# host_1.net
KiCad netlist of a schematic drawn in EAGLE
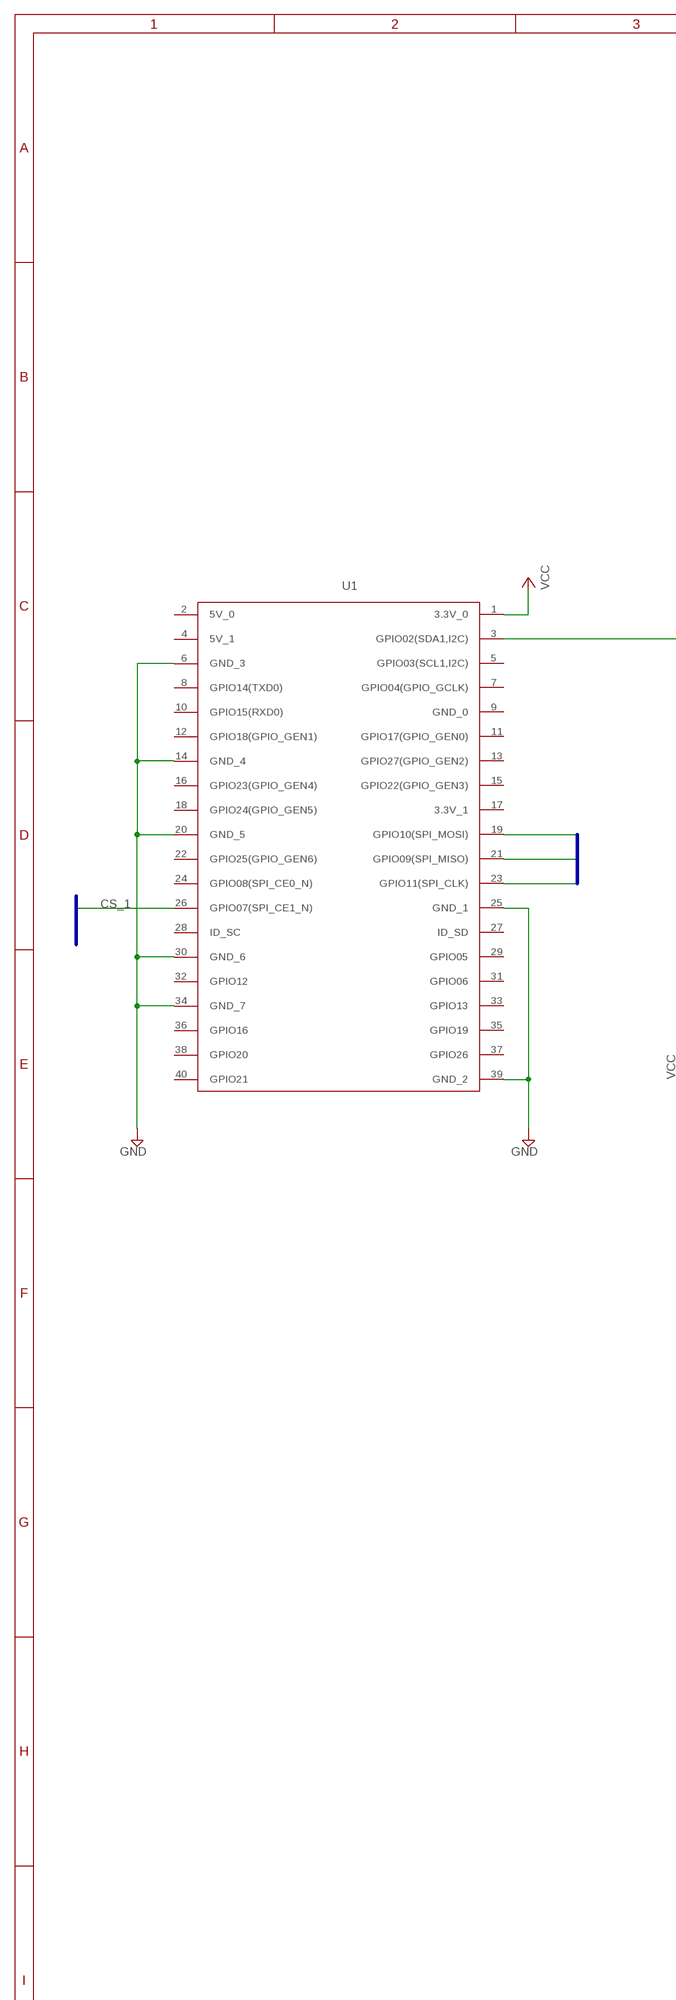
[diagram p0: schematic, sheet 1, part 1 of 2]
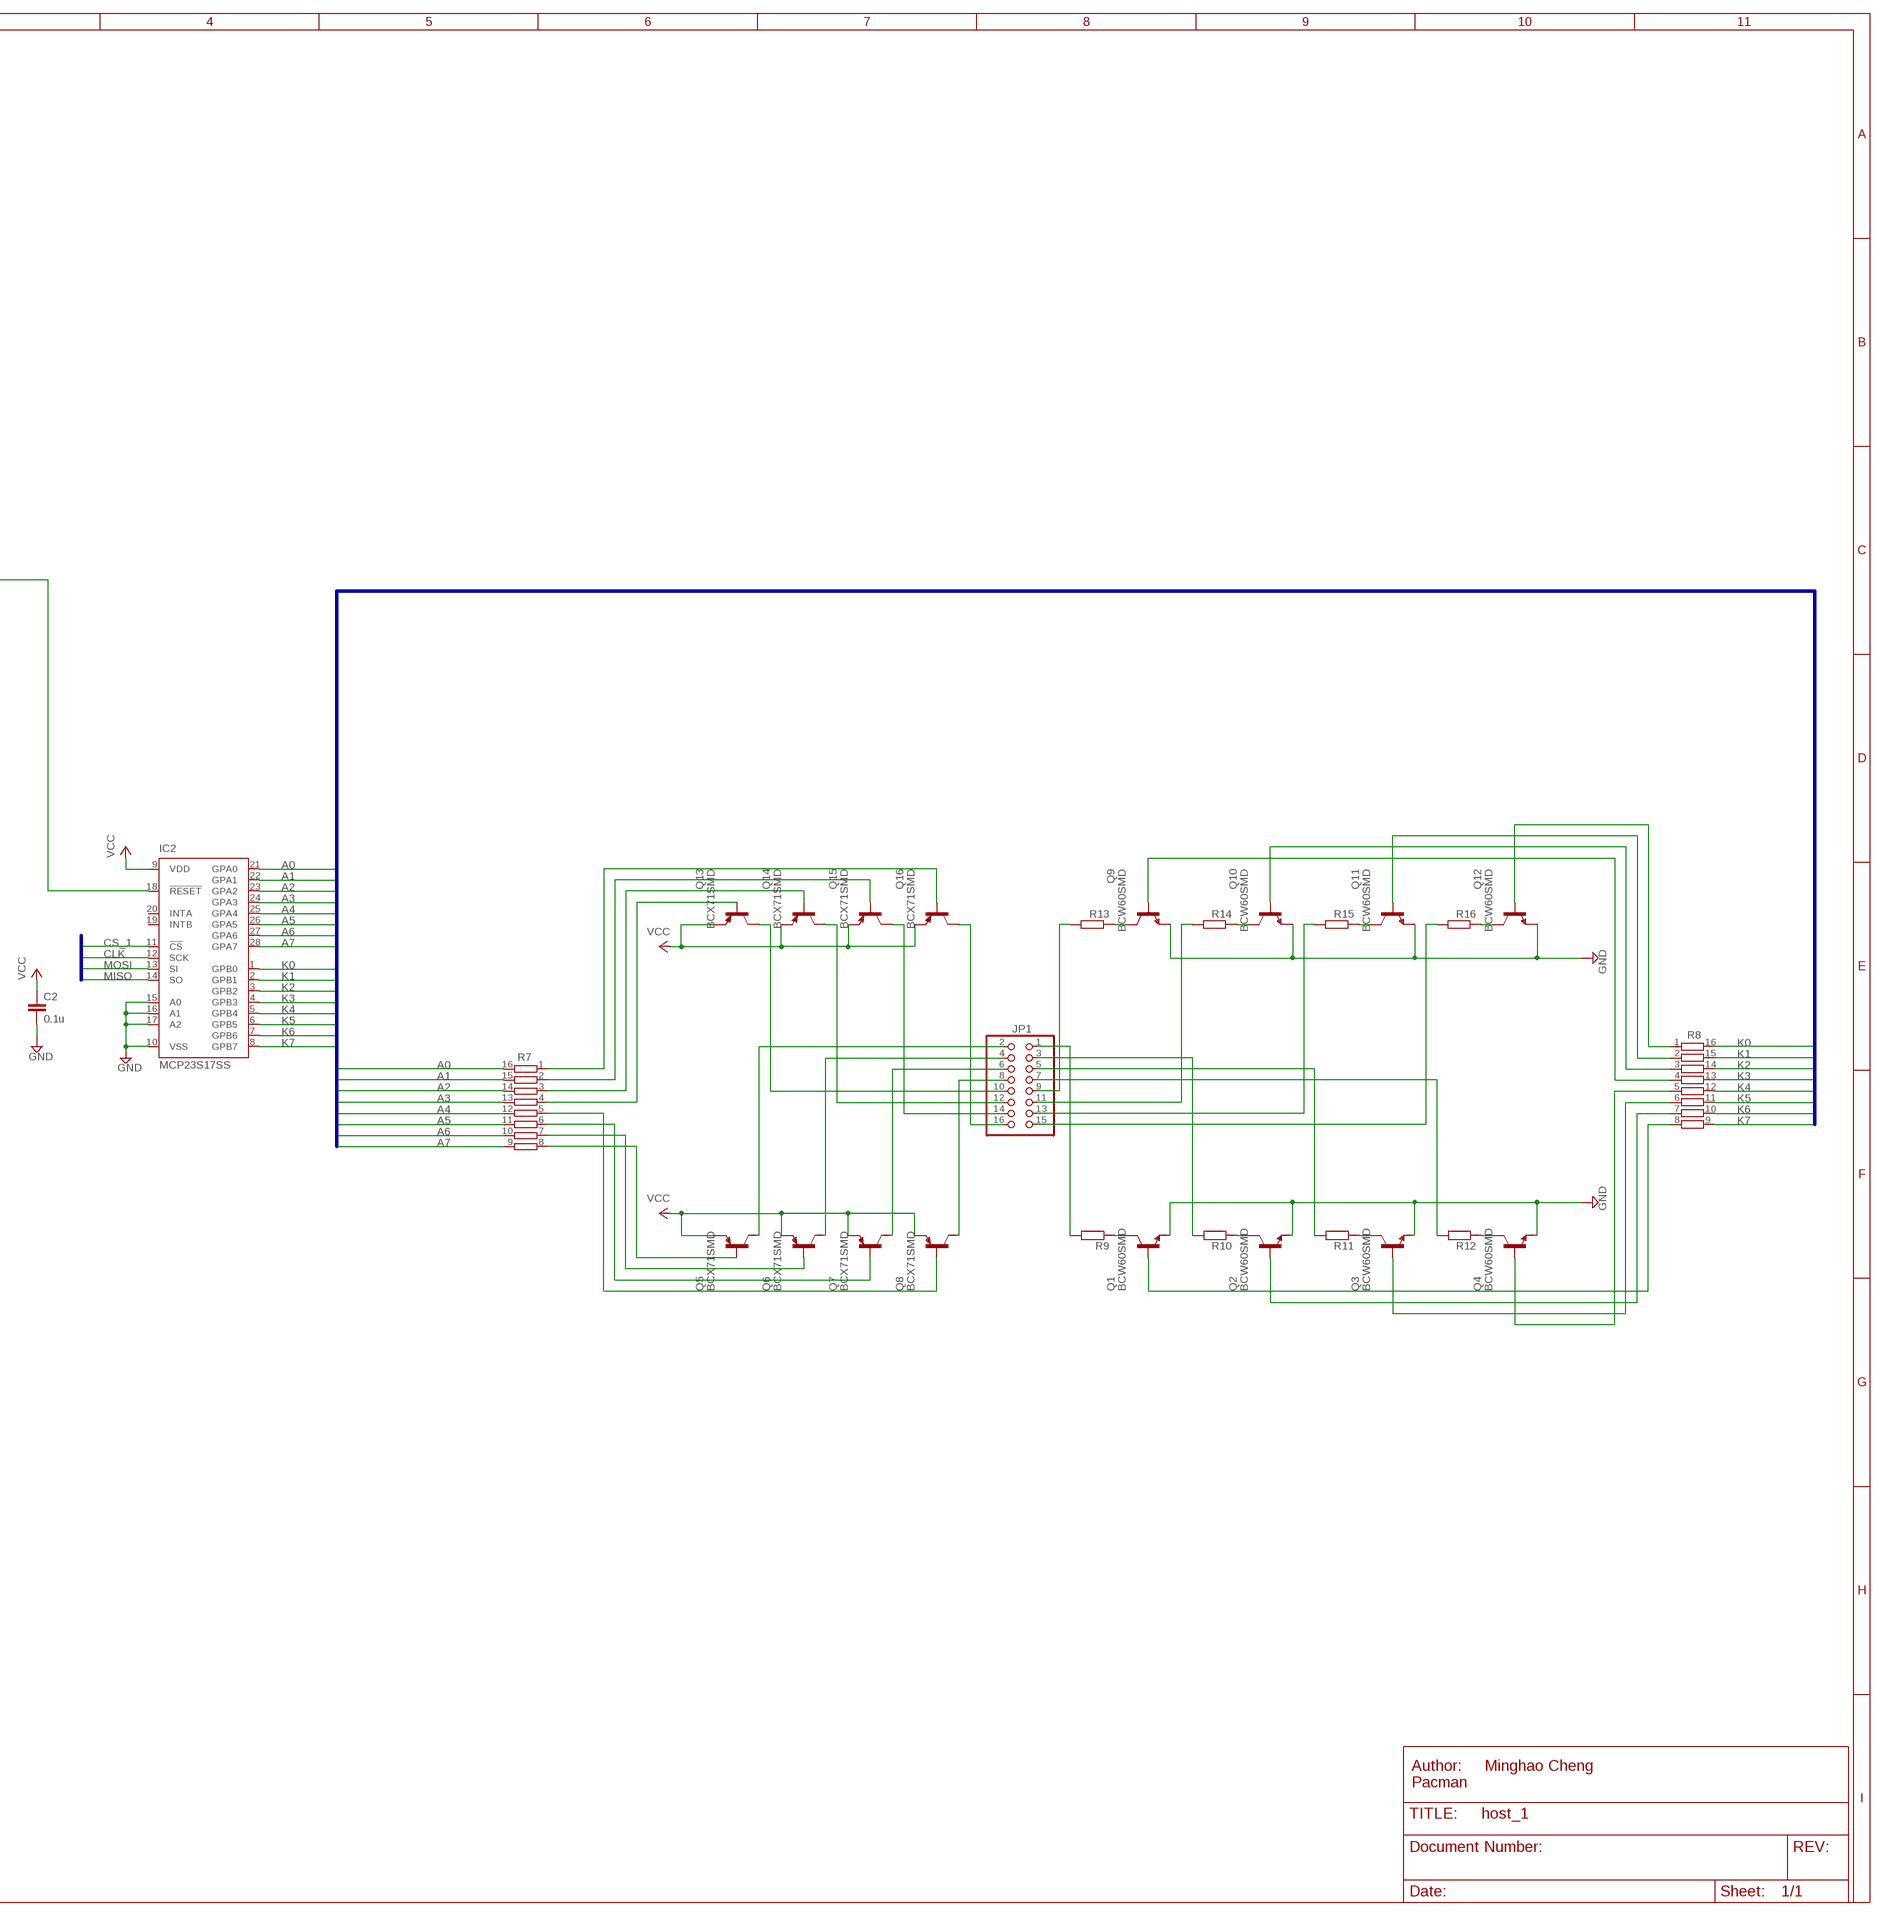
[diagram p1: schematic, sheet 1, part 2 of 2]

(export (version "E")
  (design (tool "Eeschema 10.0.6"))
  (components
    (comp (ref "C2")
      (value "0.1u")
      (footprint "eagle-import:C0805")
      (libsource (lib "eagle-import") (part "C-EUC0805"))
    )
    (comp (ref "IC2")
      (value "MCP23S17SS")
      (footprint "eagle-import:SSOP28")
      (fields (field (name "MF") "MICROCHIP") (field (name "MPN") "MCP23S17-E/SS"))
      (libsource (lib "eagle-import") (part "MCP23S17SS"))
    )
    (comp (ref "JP1")
      (value "PINHD-2X8")
      (footprint "eagle-import:2X08")
      (libsource (lib "eagle-import") (part "PINHD-2X8"))
    )
    (comp (ref "Q1")
      (value "BCW60SMD")
      (footprint "eagle-import:SOT23-BEC")
      (libsource (lib "eagle-import") (part "BCW60SMD"))
    )
    (comp (ref "Q2")
      (value "BCW60SMD")
      (footprint "eagle-import:SOT23-BEC")
      (libsource (lib "eagle-import") (part "BCW60SMD"))
    )
    (comp (ref "Q3")
      (value "BCW60SMD")
      (footprint "eagle-import:SOT23-BEC")
      (libsource (lib "eagle-import") (part "BCW60SMD"))
    )
    (comp (ref "Q4")
      (value "BCW60SMD")
      (footprint "eagle-import:SOT23-BEC")
      (libsource (lib "eagle-import") (part "BCW60SMD"))
    )
    (comp (ref "Q5")
      (value "BCX71SMD")
      (footprint "eagle-import:SOT23")
      (libsource (lib "eagle-import") (part "BCX71SMD"))
    )
    (comp (ref "Q6")
      (value "BCX71SMD")
      (footprint "eagle-import:SOT23")
      (libsource (lib "eagle-import") (part "BCX71SMD"))
    )
    (comp (ref "Q7")
      (value "BCX71SMD")
      (footprint "eagle-import:SOT23")
      (libsource (lib "eagle-import") (part "BCX71SMD"))
    )
    (comp (ref "Q8")
      (value "BCX71SMD")
      (footprint "eagle-import:SOT23")
      (libsource (lib "eagle-import") (part "BCX71SMD"))
    )
    (comp (ref "Q9")
      (value "BCW60SMD")
      (footprint "eagle-import:SOT23-BEC")
      (libsource (lib "eagle-import") (part "BCW60SMD"))
    )
    (comp (ref "Q10")
      (value "BCW60SMD")
      (footprint "eagle-import:SOT23-BEC")
      (libsource (lib "eagle-import") (part "BCW60SMD"))
    )
    (comp (ref "Q11")
      (value "BCW60SMD")
      (footprint "eagle-import:SOT23-BEC")
      (libsource (lib "eagle-import") (part "BCW60SMD"))
    )
    (comp (ref "Q12")
      (value "BCW60SMD")
      (footprint "eagle-import:SOT23-BEC")
      (libsource (lib "eagle-import") (part "BCW60SMD"))
    )
    (comp (ref "Q13")
      (value "BCX71SMD")
      (footprint "eagle-import:SOT23")
      (libsource (lib "eagle-import") (part "BCX71SMD"))
    )
    (comp (ref "Q14")
      (value "BCX71SMD")
      (footprint "eagle-import:SOT23")
      (libsource (lib "eagle-import") (part "BCX71SMD"))
    )
    (comp (ref "Q15")
      (value "BCX71SMD")
      (footprint "eagle-import:SOT23")
      (libsource (lib "eagle-import") (part "BCX71SMD"))
    )
    (comp (ref "Q16")
      (value "BCX71SMD")
      (footprint "eagle-import:SOT23")
      (libsource (lib "eagle-import") (part "BCX71SMD"))
    )
    (comp (ref "R7")
      (value "4816P-T01")
      (footprint "eagle-import:4816P")
      (fields (field (name "MF") "BOURNS, INC.") (field (name "MPN") "4816P-T01-684LF"))
      (libsource (lib "eagle-import") (part "4816P-T01"))
    )
    (comp (ref "R8")
      (value "4816P-T01")
      (footprint "eagle-import:4816P")
      (fields (field (name "MF") "BOURNS, INC.") (field (name "MPN") "4816P-T01-684LF"))
      (libsource (lib "eagle-import") (part "4816P-T01"))
    )
    (comp (ref "R9")
      (value "4.7K")
      (footprint "eagle-import:R0805")
      (libsource (lib "eagle-import") (part "R-EU_R0805"))
    )
    (comp (ref "R10")
      (value "4.7K")
      (footprint "eagle-import:R0805")
      (libsource (lib "eagle-import") (part "R-EU_R0805"))
    )
    (comp (ref "R11")
      (value "4.7K")
      (footprint "eagle-import:R0805")
      (libsource (lib "eagle-import") (part "R-EU_R0805"))
    )
    (comp (ref "R12")
      (value "4.7K")
      (footprint "eagle-import:R0805")
      (libsource (lib "eagle-import") (part "R-EU_R0805"))
    )
    (comp (ref "R13")
      (value "4.7K")
      (footprint "eagle-import:R0805")
      (libsource (lib "eagle-import") (part "R-EU_R0805"))
    )
    (comp (ref "R14")
      (value "4.7K")
      (footprint "eagle-import:R0805")
      (libsource (lib "eagle-import") (part "R-EU_R0805"))
    )
    (comp (ref "R15")
      (value "4.7K")
      (footprint "eagle-import:R0805")
      (libsource (lib "eagle-import") (part "R-EU_R0805"))
    )
    (comp (ref "R16")
      (value "4.7K")
      (footprint "eagle-import:R0805")
      (libsource (lib "eagle-import") (part "R-EU_R0805"))
    )
    (comp (ref "U1")
      (value "RASPI3_GPIO")
      (footprint "eagle-import:FE20-2")
      (libsource (lib "eagle-import") (part "RASPI3_GPIO"))
    )
  )
  (nets
    (net (code "3") (name "/A0") (class "Default")
      (node (ref "IC2") (pin "21") (pinfunction "GPA0_21") (pintype "bidirectional"))
      (node (ref "R7") (pin "16") (pinfunction "16_16") (pintype "passive"))
    )
    (net (code "4") (name "/A1") (class "Default")
      (node (ref "IC2") (pin "22") (pinfunction "GPA1_22") (pintype "bidirectional"))
      (node (ref "R7") (pin "15") (pinfunction "15_15") (pintype "passive"))
    )
    (net (code "5") (name "/A2") (class "Default")
      (node (ref "IC2") (pin "23") (pinfunction "GPA2_23") (pintype "bidirectional"))
      (node (ref "R7") (pin "14") (pinfunction "14_14") (pintype "passive"))
    )
    (net (code "6") (name "/A3") (class "Default")
      (node (ref "IC2") (pin "24") (pinfunction "GPA3_24") (pintype "bidirectional"))
      (node (ref "R7") (pin "13") (pinfunction "13_13") (pintype "passive"))
    )
    (net (code "7") (name "/A4") (class "Default")
      (node (ref "IC2") (pin "25") (pinfunction "GPA4_25") (pintype "bidirectional"))
      (node (ref "R7") (pin "12") (pinfunction "12_12") (pintype "passive"))
    )
    (net (code "8") (name "/A5") (class "Default")
      (node (ref "IC2") (pin "26") (pinfunction "GPA5_26") (pintype "bidirectional"))
      (node (ref "R7") (pin "11") (pinfunction "11_11") (pintype "passive"))
    )
    (net (code "9") (name "/A6") (class "Default")
      (node (ref "IC2") (pin "27") (pinfunction "GPA6_27") (pintype "bidirectional"))
      (node (ref "R7") (pin "10") (pinfunction "10_10") (pintype "passive"))
    )
    (net (code "10") (name "/A7") (class "Default")
      (node (ref "IC2") (pin "28") (pinfunction "GPA7_28") (pintype "bidirectional"))
      (node (ref "R7") (pin "9") (pinfunction "9_9") (pintype "passive"))
    )
    (net (code "11") (name "/CLK") (class "Default")
      (node (ref "IC2") (pin "12") (pinfunction "SCK_12") (pintype "input"))
      (node (ref "U1") (pin "23") (pinfunction "GPIO11(SPI_CLK)_23") (pintype "bidirectional"))
    )
    (net (code "12") (name "/CS_1") (class "Default")
      (node (ref "IC2") (pin "11") (pinfunction "~{CS}_11") (pintype "input"))
      (node (ref "U1") (pin "26") (pinfunction "GPIO07(SPI_CE1_N)_26") (pintype "bidirectional"))
    )
    (net (code "13") (name "/K0") (class "Default")
      (node (ref "IC2") (pin "1") (pinfunction "GPB0_1") (pintype "bidirectional"))
      (node (ref "R8") (pin "16") (pinfunction "16_16") (pintype "passive"))
    )
    (net (code "14") (name "/K1") (class "Default")
      (node (ref "IC2") (pin "2") (pinfunction "GPB1_2") (pintype "bidirectional"))
      (node (ref "R8") (pin "15") (pinfunction "15_15") (pintype "passive"))
    )
    (net (code "15") (name "/K2") (class "Default")
      (node (ref "IC2") (pin "3") (pinfunction "GPB2_3") (pintype "bidirectional"))
      (node (ref "R8") (pin "14") (pinfunction "14_14") (pintype "passive"))
    )
    (net (code "16") (name "/K3") (class "Default")
      (node (ref "IC2") (pin "4") (pinfunction "GPB3_4") (pintype "bidirectional"))
      (node (ref "R8") (pin "13") (pinfunction "13_13") (pintype "passive"))
    )
    (net (code "17") (name "/K4") (class "Default")
      (node (ref "IC2") (pin "5") (pinfunction "GPB4_5") (pintype "bidirectional"))
      (node (ref "R8") (pin "12") (pinfunction "12_12") (pintype "passive"))
    )
    (net (code "18") (name "/K5") (class "Default")
      (node (ref "IC2") (pin "6") (pinfunction "GPB5_6") (pintype "bidirectional"))
      (node (ref "R8") (pin "11") (pinfunction "11_11") (pintype "passive"))
    )
    (net (code "19") (name "/K6") (class "Default")
      (node (ref "IC2") (pin "7") (pinfunction "GPB6_7") (pintype "bidirectional"))
      (node (ref "R8") (pin "10") (pinfunction "10_10") (pintype "passive"))
    )
    (net (code "20") (name "/K7") (class "Default")
      (node (ref "IC2") (pin "8") (pinfunction "GPB7_8") (pintype "bidirectional"))
      (node (ref "R8") (pin "9") (pinfunction "9_9") (pintype "passive"))
    )
    (net (code "21") (name "/MISO") (class "Default")
      (node (ref "IC2") (pin "14") (pinfunction "SO_14") (pintype "output"))
      (node (ref "U1") (pin "21") (pinfunction "GPIO09(SPI_MISO)_21") (pintype "bidirectional"))
    )
    (net (code "22") (name "/SPI_PI:CLK") (class "Default")
      (node (ref "IC2") (pin "13") (pinfunction "SI_13") (pintype "input"))
      (node (ref "U1") (pin "19") (pinfunction "GPIO10(SPI_MOSI)_19") (pintype "bidirectional"))
    )
    (net (code "24") (name "GND") (class "Default")
      (node (ref "C2") (pin "2") (pinfunction "2_2") (pintype "passive"))
      (node (ref "IC2") (pin "10") (pinfunction "VSS_10") (pintype "power_in"))
      (node (ref "IC2") (pin "15") (pinfunction "A0_15") (pintype "input"))
      (node (ref "IC2") (pin "16") (pinfunction "A1_16") (pintype "input"))
      (node (ref "IC2") (pin "17") (pinfunction "A2_17") (pintype "input"))
      (node (ref "Q1") (pin "E") (pinfunction "E_E") (pintype "passive"))
      (node (ref "Q10") (pin "E") (pinfunction "E_E") (pintype "passive"))
      (node (ref "Q11") (pin "E") (pinfunction "E_E") (pintype "passive"))
      (node (ref "Q12") (pin "E") (pinfunction "E_E") (pintype "passive"))
      (node (ref "Q2") (pin "E") (pinfunction "E_E") (pintype "passive"))
      (node (ref "Q3") (pin "E") (pinfunction "E_E") (pintype "passive"))
      (node (ref "Q4") (pin "E") (pinfunction "E_E") (pintype "passive"))
      (node (ref "Q9") (pin "E") (pinfunction "E_E") (pintype "passive"))
      (node (ref "U1") (pin "14") (pinfunction "GND_4_14") (pintype "bidirectional"))
      (node (ref "U1") (pin "20") (pinfunction "GND_5_20") (pintype "bidirectional"))
      (node (ref "U1") (pin "25") (pinfunction "GND_1_25") (pintype "bidirectional"))
      (node (ref "U1") (pin "30") (pinfunction "GND_6_30") (pintype "bidirectional"))
      (node (ref "U1") (pin "34") (pinfunction "GND_7_34") (pintype "bidirectional"))
      (node (ref "U1") (pin "39") (pinfunction "GND_2_39") (pintype "bidirectional"))
      (node (ref "U1") (pin "6") (pinfunction "GND_3_6") (pintype "bidirectional"))
    )
    (net (code "25") (name "Net-(IC2-~{RESET})") (class "Default")
      (node (ref "IC2") (pin "18") (pinfunction "~{RESET}_18") (pintype "input"))
      (node (ref "U1") (pin "3") (pinfunction "GPIO02(SDA1,I2C)_3") (pintype "bidirectional"))
    )
    (net (code "26") (name "Net-(JP1-Pad1)") (class "Default")
      (node (ref "JP1") (pin "1") (pinfunction "1_1") (pintype "passive"))
      (node (ref "R9") (pin "2") (pinfunction "2_2") (pintype "passive"))
    )
    (net (code "27") (name "Net-(JP1-Pad3)") (class "Default")
      (node (ref "JP1") (pin "3") (pinfunction "3_3") (pintype "passive"))
      (node (ref "R10") (pin "2") (pinfunction "2_2") (pintype "passive"))
    )
    (net (code "28") (name "Net-(JP1-Pad5)") (class "Default")
      (node (ref "JP1") (pin "5") (pinfunction "5_5") (pintype "passive"))
      (node (ref "R11") (pin "2") (pinfunction "2_2") (pintype "passive"))
    )
    (net (code "29") (name "Net-(JP1-Pad7)") (class "Default")
      (node (ref "JP1") (pin "7") (pinfunction "7_7") (pintype "passive"))
      (node (ref "R12") (pin "2") (pinfunction "2_2") (pintype "passive"))
    )
    (net (code "30") (name "Net-(JP1-Pad9)") (class "Default")
      (node (ref "JP1") (pin "9") (pinfunction "9_9") (pintype "passive"))
      (node (ref "R13") (pin "2") (pinfunction "2_2") (pintype "passive"))
    )
    (net (code "31") (name "Net-(JP1-Pad11)") (class "Default")
      (node (ref "JP1") (pin "11") (pinfunction "11_11") (pintype "passive"))
      (node (ref "R14") (pin "2") (pinfunction "2_2") (pintype "passive"))
    )
    (net (code "32") (name "Net-(JP1-Pad13)") (class "Default")
      (node (ref "JP1") (pin "13") (pinfunction "13_13") (pintype "passive"))
      (node (ref "R15") (pin "2") (pinfunction "2_2") (pintype "passive"))
    )
    (net (code "33") (name "Net-(JP1-Pad15)") (class "Default")
      (node (ref "JP1") (pin "15") (pinfunction "15_15") (pintype "passive"))
      (node (ref "R16") (pin "2") (pinfunction "2_2") (pintype "passive"))
    )
    (net (code "34") (name "Net-(Q1-PadB)") (class "Default")
      (node (ref "Q1") (pin "B") (pinfunction "B_B") (pintype "passive"))
      (node (ref "R8") (pin "8") (pinfunction "8_8") (pintype "passive"))
    )
    (net (code "35") (name "Net-(Q1-PadC)") (class "Default")
      (node (ref "Q1") (pin "C") (pinfunction "C_C") (pintype "passive"))
      (node (ref "R9") (pin "1") (pinfunction "1_1") (pintype "passive"))
    )
    (net (code "36") (name "Net-(Q2-PadB)") (class "Default")
      (node (ref "Q2") (pin "B") (pinfunction "B_B") (pintype "passive"))
      (node (ref "R8") (pin "7") (pinfunction "7_7") (pintype "passive"))
    )
    (net (code "37") (name "Net-(Q2-PadC)") (class "Default")
      (node (ref "Q2") (pin "C") (pinfunction "C_C") (pintype "passive"))
      (node (ref "R10") (pin "1") (pinfunction "1_1") (pintype "passive"))
    )
    (net (code "38") (name "Net-(Q3-PadB)") (class "Default")
      (node (ref "Q3") (pin "B") (pinfunction "B_B") (pintype "passive"))
      (node (ref "R8") (pin "6") (pinfunction "6_6") (pintype "passive"))
    )
    (net (code "39") (name "Net-(Q3-PadC)") (class "Default")
      (node (ref "Q3") (pin "C") (pinfunction "C_C") (pintype "passive"))
      (node (ref "R11") (pin "1") (pinfunction "1_1") (pintype "passive"))
    )
    (net (code "40") (name "Net-(Q4-PadB)") (class "Default")
      (node (ref "Q4") (pin "B") (pinfunction "B_B") (pintype "passive"))
      (node (ref "R8") (pin "5") (pinfunction "5_5") (pintype "passive"))
    )
    (net (code "41") (name "Net-(Q4-PadC)") (class "Default")
      (node (ref "Q4") (pin "C") (pinfunction "C_C") (pintype "passive"))
      (node (ref "R12") (pin "1") (pinfunction "1_1") (pintype "passive"))
    )
    (net (code "42") (name "Net-(Q5-B)") (class "Default")
      (node (ref "Q5") (pin "1") (pinfunction "B_1") (pintype "passive"))
      (node (ref "R7") (pin "8") (pinfunction "8_8") (pintype "passive"))
    )
    (net (code "43") (name "Net-(Q5-C)") (class "Default")
      (node (ref "JP1") (pin "2") (pinfunction "2_2") (pintype "passive"))
      (node (ref "Q5") (pin "3") (pinfunction "C_3") (pintype "passive"))
    )
    (net (code "44") (name "Net-(Q6-B)") (class "Default")
      (node (ref "Q6") (pin "1") (pinfunction "B_1") (pintype "passive"))
      (node (ref "R7") (pin "7") (pinfunction "7_7") (pintype "passive"))
    )
    (net (code "45") (name "Net-(Q6-C)") (class "Default")
      (node (ref "JP1") (pin "4") (pinfunction "4_4") (pintype "passive"))
      (node (ref "Q6") (pin "3") (pinfunction "C_3") (pintype "passive"))
    )
    (net (code "46") (name "Net-(Q7-B)") (class "Default")
      (node (ref "Q7") (pin "1") (pinfunction "B_1") (pintype "passive"))
      (node (ref "R7") (pin "6") (pinfunction "6_6") (pintype "passive"))
    )
    (net (code "47") (name "Net-(Q7-C)") (class "Default")
      (node (ref "JP1") (pin "6") (pinfunction "6_6") (pintype "passive"))
      (node (ref "Q7") (pin "3") (pinfunction "C_3") (pintype "passive"))
    )
    (net (code "48") (name "Net-(Q8-B)") (class "Default")
      (node (ref "Q8") (pin "1") (pinfunction "B_1") (pintype "passive"))
      (node (ref "R7") (pin "5") (pinfunction "5_5") (pintype "passive"))
    )
    (net (code "49") (name "Net-(Q8-C)") (class "Default")
      (node (ref "JP1") (pin "8") (pinfunction "8_8") (pintype "passive"))
      (node (ref "Q8") (pin "3") (pinfunction "C_3") (pintype "passive"))
    )
    (net (code "50") (name "Net-(Q9-PadB)") (class "Default")
      (node (ref "Q9") (pin "B") (pinfunction "B_B") (pintype "passive"))
      (node (ref "R8") (pin "4") (pinfunction "4_4") (pintype "passive"))
    )
    (net (code "51") (name "Net-(Q9-PadC)") (class "Default")
      (node (ref "Q9") (pin "C") (pinfunction "C_C") (pintype "passive"))
      (node (ref "R13") (pin "1") (pinfunction "1_1") (pintype "passive"))
    )
    (net (code "52") (name "Net-(Q10-PadB)") (class "Default")
      (node (ref "Q10") (pin "B") (pinfunction "B_B") (pintype "passive"))
      (node (ref "R8") (pin "3") (pinfunction "3_3") (pintype "passive"))
    )
    (net (code "53") (name "Net-(Q10-PadC)") (class "Default")
      (node (ref "Q10") (pin "C") (pinfunction "C_C") (pintype "passive"))
      (node (ref "R14") (pin "1") (pinfunction "1_1") (pintype "passive"))
    )
    (net (code "54") (name "Net-(Q11-PadB)") (class "Default")
      (node (ref "Q11") (pin "B") (pinfunction "B_B") (pintype "passive"))
      (node (ref "R8") (pin "2") (pinfunction "2_2") (pintype "passive"))
    )
    (net (code "55") (name "Net-(Q11-PadC)") (class "Default")
      (node (ref "Q11") (pin "C") (pinfunction "C_C") (pintype "passive"))
      (node (ref "R15") (pin "1") (pinfunction "1_1") (pintype "passive"))
    )
    (net (code "56") (name "Net-(Q12-PadB)") (class "Default")
      (node (ref "Q12") (pin "B") (pinfunction "B_B") (pintype "passive"))
      (node (ref "R8") (pin "1") (pinfunction "1_1") (pintype "passive"))
    )
    (net (code "57") (name "Net-(Q12-PadC)") (class "Default")
      (node (ref "Q12") (pin "C") (pinfunction "C_C") (pintype "passive"))
      (node (ref "R16") (pin "1") (pinfunction "1_1") (pintype "passive"))
    )
    (net (code "58") (name "Net-(Q13-B)") (class "Default")
      (node (ref "Q13") (pin "1") (pinfunction "B_1") (pintype "passive"))
      (node (ref "R7") (pin "4") (pinfunction "4_4") (pintype "passive"))
    )
    (net (code "59") (name "Net-(Q13-C)") (class "Default")
      (node (ref "JP1") (pin "10") (pinfunction "10_10") (pintype "passive"))
      (node (ref "Q13") (pin "3") (pinfunction "C_3") (pintype "passive"))
    )
    (net (code "60") (name "Net-(Q14-B)") (class "Default")
      (node (ref "Q14") (pin "1") (pinfunction "B_1") (pintype "passive"))
      (node (ref "R7") (pin "3") (pinfunction "3_3") (pintype "passive"))
    )
    (net (code "61") (name "Net-(Q14-C)") (class "Default")
      (node (ref "JP1") (pin "12") (pinfunction "12_12") (pintype "passive"))
      (node (ref "Q14") (pin "3") (pinfunction "C_3") (pintype "passive"))
    )
    (net (code "62") (name "Net-(Q15-B)") (class "Default")
      (node (ref "Q15") (pin "1") (pinfunction "B_1") (pintype "passive"))
      (node (ref "R7") (pin "2") (pinfunction "2_2") (pintype "passive"))
    )
    (net (code "63") (name "Net-(Q15-C)") (class "Default")
      (node (ref "JP1") (pin "14") (pinfunction "14_14") (pintype "passive"))
      (node (ref "Q15") (pin "3") (pinfunction "C_3") (pintype "passive"))
    )
    (net (code "64") (name "Net-(Q16-B)") (class "Default")
      (node (ref "Q16") (pin "1") (pinfunction "B_1") (pintype "passive"))
      (node (ref "R7") (pin "1") (pinfunction "1_1") (pintype "passive"))
    )
    (net (code "65") (name "Net-(Q16-C)") (class "Default")
      (node (ref "JP1") (pin "16") (pinfunction "16_16") (pintype "passive"))
      (node (ref "Q16") (pin "3") (pinfunction "C_3") (pintype "passive"))
    )
    (net (code "66") (name "VCC") (class "Default")
      (node (ref "C2") (pin "1") (pinfunction "1_1") (pintype "passive"))
      (node (ref "IC2") (pin "9") (pinfunction "VDD_9") (pintype "power_in"))
      (node (ref "Q13") (pin "2") (pinfunction "E_2") (pintype "passive"))
      (node (ref "Q14") (pin "2") (pinfunction "E_2") (pintype "passive"))
      (node (ref "Q15") (pin "2") (pinfunction "E_2") (pintype "passive"))
      (node (ref "Q16") (pin "2") (pinfunction "E_2") (pintype "passive"))
      (node (ref "Q5") (pin "2") (pinfunction "E_2") (pintype "passive"))
      (node (ref "Q6") (pin "2") (pinfunction "E_2") (pintype "passive"))
      (node (ref "Q7") (pin "2") (pinfunction "E_2") (pintype "passive"))
      (node (ref "Q8") (pin "2") (pinfunction "E_2") (pintype "passive"))
      (node (ref "U1") (pin "1") (pinfunction "3.3V_0_1") (pintype "bidirectional"))
    )
    (net (code "67") (name "unconnected-(IC2-INTA-Pad20)") (class "Default")
      (node (ref "IC2") (pin "20") (pinfunction "INTA_20") (pintype "output"))
    )
    (net (code "68") (name "unconnected-(IC2-INTB-Pad19)") (class "Default")
      (node (ref "IC2") (pin "19") (pinfunction "INTB_19") (pintype "output"))
    )
    (net (code "69") (name "unconnected-(U1-3.3V_1-Pad17)") (class "Default")
      (node (ref "U1") (pin "17") (pinfunction "3.3V_1_17") (pintype "bidirectional"))
    )
    (net (code "70") (name "unconnected-(U1-5V_0-Pad2)") (class "Default")
      (node (ref "U1") (pin "2") (pinfunction "5V_0_2") (pintype "bidirectional"))
    )
    (net (code "71") (name "unconnected-(U1-5V_1-Pad4)") (class "Default")
      (node (ref "U1") (pin "4") (pinfunction "5V_1_4") (pintype "bidirectional"))
    )
    (net (code "72") (name "unconnected-(U1-GND_0-Pad9)") (class "Default")
      (node (ref "U1") (pin "9") (pinfunction "GND_0_9") (pintype "bidirectional"))
    )
    (net (code "73") (name "unconnected-(U1-GPIO03(SCL1,I2C)-Pad5)") (class "Default")
      (node (ref "U1") (pin "5") (pinfunction "GPIO03(SCL1,I2C)_5") (pintype "bidirectional"))
    )
    (net (code "74") (name "unconnected-(U1-GPIO04(GPIO_GCLK)-Pad7)") (class "Default")
      (node (ref "U1") (pin "7") (pinfunction "GPIO04(GPIO_GCLK)_7") (pintype "bidirectional"))
    )
    (net (code "75") (name "unconnected-(U1-GPIO05-Pad29)") (class "Default")
      (node (ref "U1") (pin "29") (pinfunction "GPIO05_29") (pintype "bidirectional"))
    )
    (net (code "76") (name "unconnected-(U1-GPIO06-Pad31)") (class "Default")
      (node (ref "U1") (pin "31") (pinfunction "GPIO06_31") (pintype "bidirectional"))
    )
    (net (code "77") (name "unconnected-(U1-GPIO08(SPI_CE0_N)-Pad24)") (class "Default")
      (node (ref "U1") (pin "24") (pinfunction "GPIO08(SPI_CE0_N)_24") (pintype "bidirectional"))
    )
    (net (code "78") (name "unconnected-(U1-GPIO12-Pad32)") (class "Default")
      (node (ref "U1") (pin "32") (pinfunction "GPIO12_32") (pintype "bidirectional"))
    )
    (net (code "79") (name "unconnected-(U1-GPIO13-Pad33)") (class "Default")
      (node (ref "U1") (pin "33") (pinfunction "GPIO13_33") (pintype "bidirectional"))
    )
    (net (code "80") (name "unconnected-(U1-GPIO14(TXD0)-Pad8)") (class "Default")
      (node (ref "U1") (pin "8") (pinfunction "GPIO14(TXD0)_8") (pintype "bidirectional"))
    )
    (net (code "81") (name "unconnected-(U1-GPIO15(RXD0)-Pad10)") (class "Default")
      (node (ref "U1") (pin "10") (pinfunction "GPIO15(RXD0)_10") (pintype "bidirectional"))
    )
    (net (code "82") (name "unconnected-(U1-GPIO16-Pad36)") (class "Default")
      (node (ref "U1") (pin "36") (pinfunction "GPIO16_36") (pintype "bidirectional"))
    )
    (net (code "83") (name "unconnected-(U1-GPIO17(GPIO_GEN0)-Pad11)") (class "Default")
      (node (ref "U1") (pin "11") (pinfunction "GPIO17(GPIO_GEN0)_11") (pintype "bidirectional"))
    )
    (net (code "84") (name "unconnected-(U1-GPIO18(GPIO_GEN1)-Pad12)") (class "Default")
      (node (ref "U1") (pin "12") (pinfunction "GPIO18(GPIO_GEN1)_12") (pintype "bidirectional"))
    )
    (net (code "85") (name "unconnected-(U1-GPIO19-Pad35)") (class "Default")
      (node (ref "U1") (pin "35") (pinfunction "GPIO19_35") (pintype "bidirectional"))
    )
    (net (code "86") (name "unconnected-(U1-GPIO20-Pad38)") (class "Default")
      (node (ref "U1") (pin "38") (pinfunction "GPIO20_38") (pintype "bidirectional"))
    )
    (net (code "87") (name "unconnected-(U1-GPIO21-Pad40)") (class "Default")
      (node (ref "U1") (pin "40") (pinfunction "GPIO21_40") (pintype "bidirectional"))
    )
    (net (code "88") (name "unconnected-(U1-GPIO22(GPIO_GEN3)-Pad15)") (class "Default")
      (node (ref "U1") (pin "15") (pinfunction "GPIO22(GPIO_GEN3)_15") (pintype "bidirectional"))
    )
    (net (code "89") (name "unconnected-(U1-GPIO23(GPIO_GEN4)-Pad16)") (class "Default")
      (node (ref "U1") (pin "16") (pinfunction "GPIO23(GPIO_GEN4)_16") (pintype "bidirectional"))
    )
    (net (code "90") (name "unconnected-(U1-GPIO24(GPIO_GEN5)-Pad18)") (class "Default")
      (node (ref "U1") (pin "18") (pinfunction "GPIO24(GPIO_GEN5)_18") (pintype "bidirectional"))
    )
    (net (code "91") (name "unconnected-(U1-GPIO25(GPIO_GEN6)-Pad22)") (class "Default")
      (node (ref "U1") (pin "22") (pinfunction "GPIO25(GPIO_GEN6)_22") (pintype "bidirectional"))
    )
    (net (code "92") (name "unconnected-(U1-GPIO26-Pad37)") (class "Default")
      (node (ref "U1") (pin "37") (pinfunction "GPIO26_37") (pintype "bidirectional"))
    )
    (net (code "93") (name "unconnected-(U1-GPIO27(GPIO_GEN2)-Pad13)") (class "Default")
      (node (ref "U1") (pin "13") (pinfunction "GPIO27(GPIO_GEN2)_13") (pintype "bidirectional"))
    )
    (net (code "94") (name "unconnected-(U1-ID_SC-Pad28)") (class "Default")
      (node (ref "U1") (pin "28") (pinfunction "ID_SC_28") (pintype "bidirectional"))
    )
    (net (code "95") (name "unconnected-(U1-ID_SD-Pad27)") (class "Default")
      (node (ref "U1") (pin "27") (pinfunction "ID_SD_27") (pintype "bidirectional"))
    )
  )
)
